# LED_Driver_-_2.net
KiCad netlist of a schematic drawn in Altium Designer
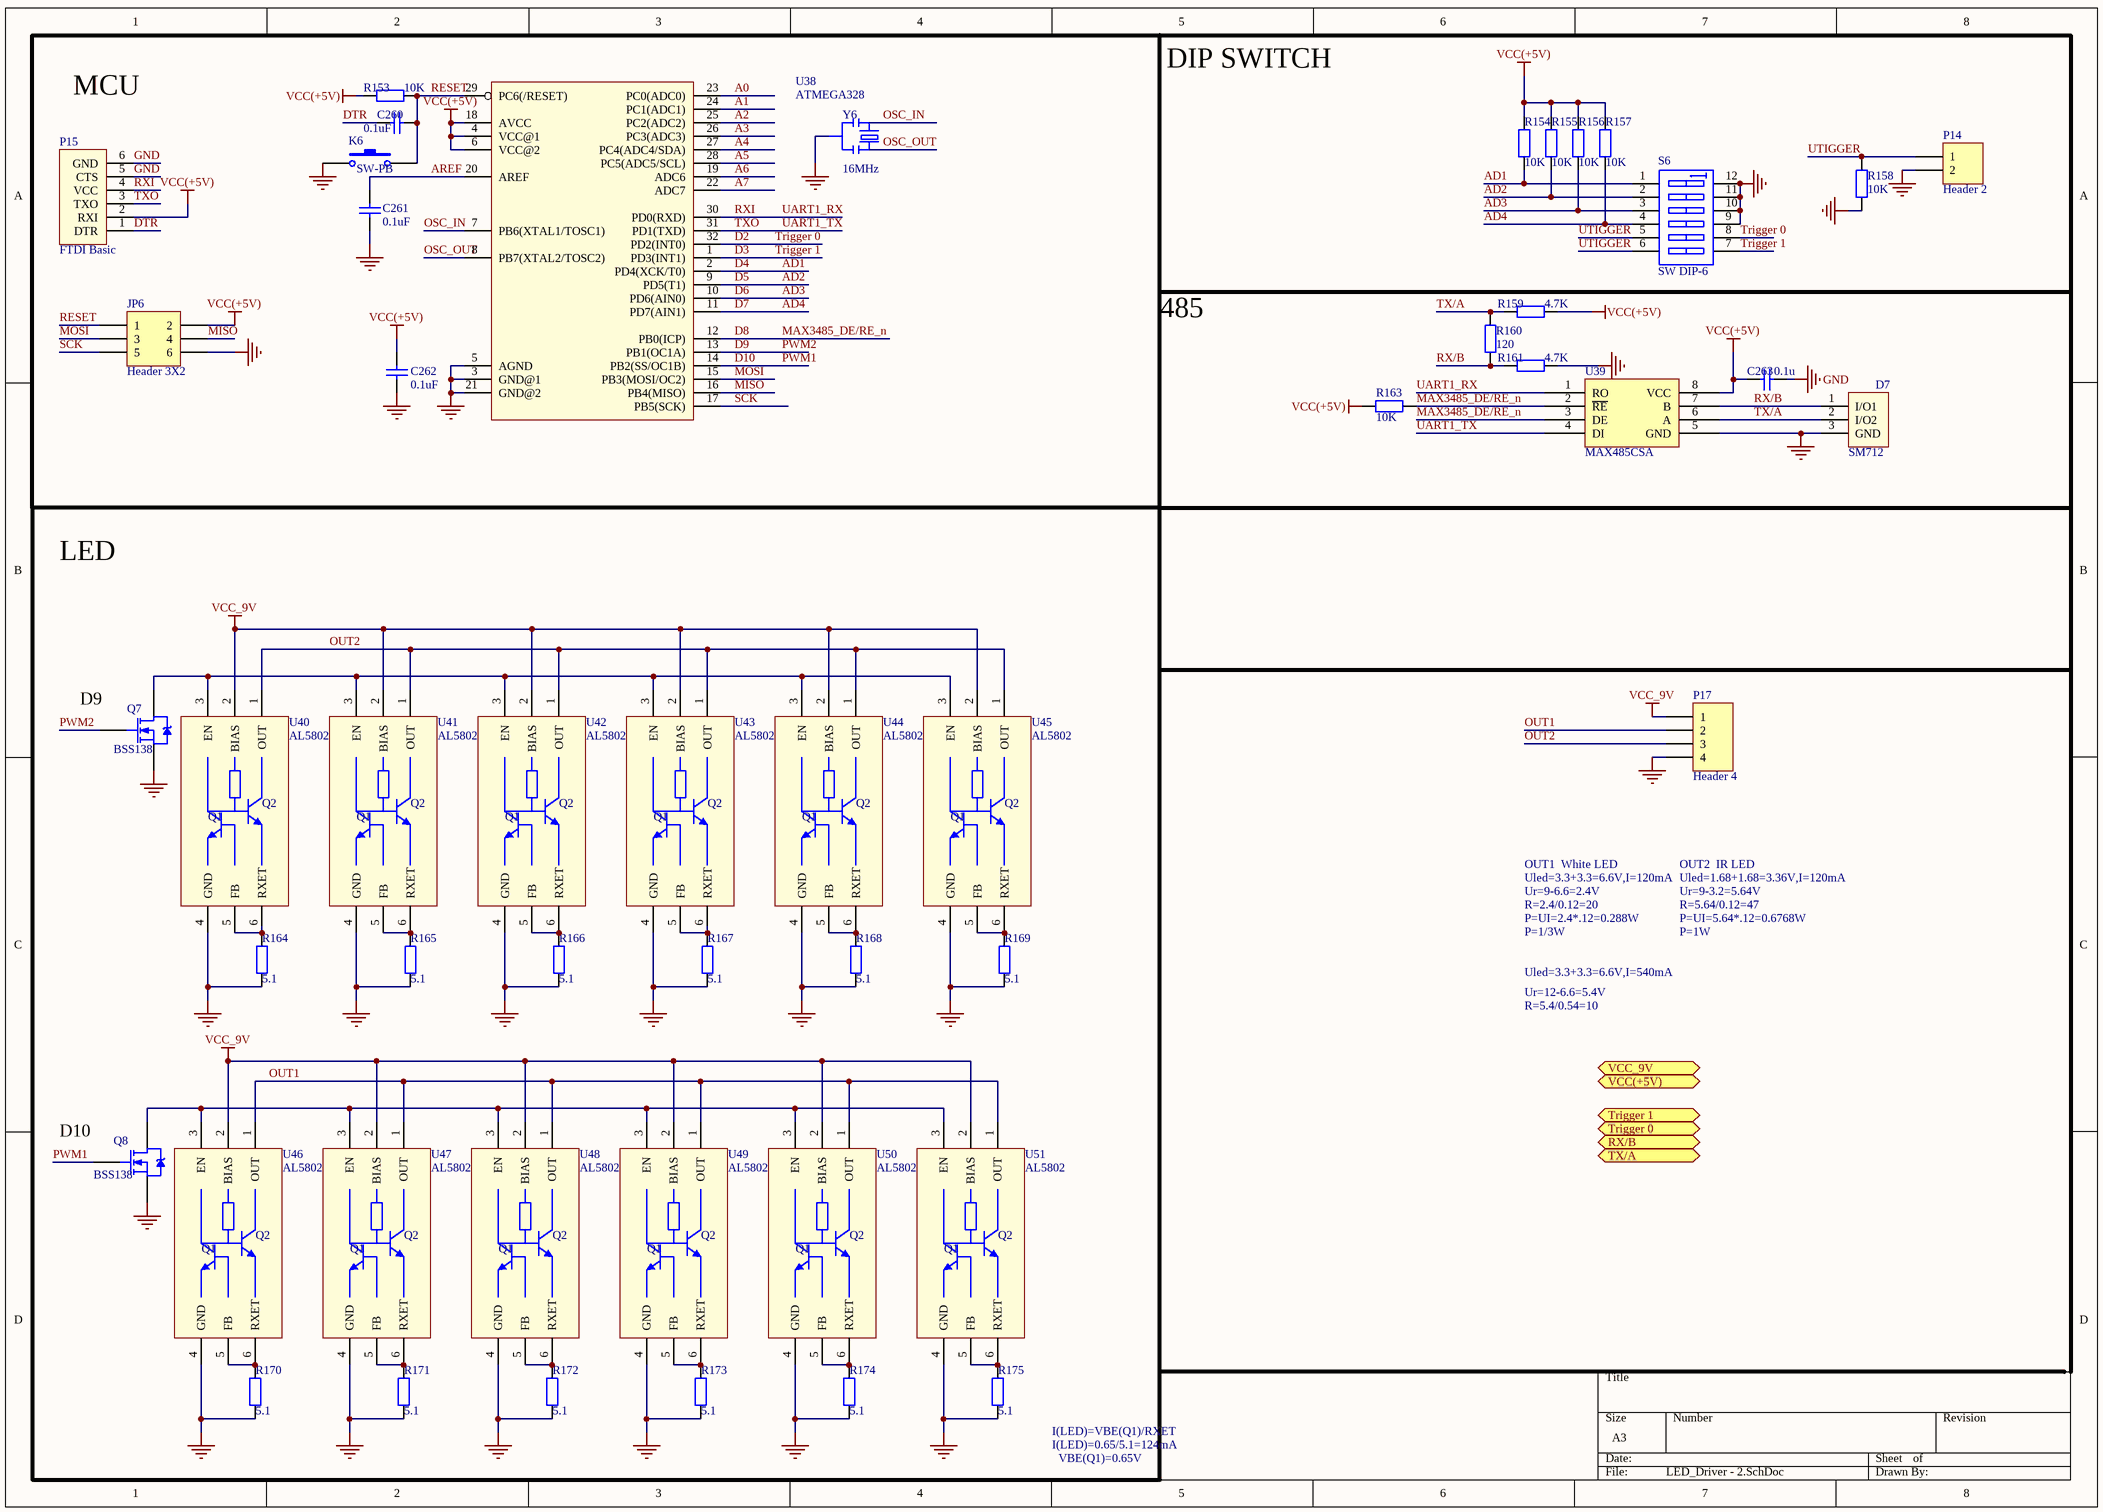
[diagram p0: LED_Driver - 2.SchDoc]

(export (version "E")
  (design (tool "Eeschema 10.0.6"))
  (components
    (comp (ref "C260")
      (value "0.1uF")
      (footprint "C0603")
      (description "Capacitor")
      (fields (field (name "IPARTNUMBER") "C100nF25V10%X7R") (field (name "VOLTAGE") "25V"))
      (libsource (lib "Schlib1") (part "CAP SMT C100nF25V10%X7R"))
    )
    (comp (ref "C261")
      (value "0.1uF")
      (footprint "C0603")
      (description "Capacitor")
      (fields (field (name "IPARTNUMBER") "C100nF25V10%X7R") (field (name "VOLTAGE") "25V"))
      (libsource (lib "Schlib1") (part "CAP SMT C100nF25V10%X7R"))
    )
    (comp (ref "C262")
      (value "0.1uF")
      (footprint "C0603")
      (description "Capacitor")
      (fields (field (name "IPARTNUMBER") "C100nF25V10%X7R") (field (name "VOLTAGE") "25V"))
      (libsource (lib "Schlib1") (part "CAP SMT C100nF25V10%X7R"))
    )
    (comp (ref "C263")
      (value "0.1u")
      (footprint "C0603")
      (description "Capacitor")
      (fields (field (name "PUBLISHER") "Altium Limited"))
      (libsource (lib "Miscellaneous Devices") (part "Cap"))
    )
    (comp (ref "D7")
      (value "SM712")
      (footprint "SOT23-3")
      (libsource (lib "STM32F4_CAM V2.0") (part "SM712"))
    )
    (comp (ref "JP6")
      (value "Header 3X2")
      (footprint "MHDR1X6")
      (description "Header, 3-Pin, Dual row")
      (fields (field (name "PUBLISHER") "Altium Limited"))
      (libsource (lib "Miscellaneous Connectors") (part "Header 3X2"))
    )
    (comp (ref "K6")
      (value "SW-PB")
      (footprint "157SW")
      (description "Switch")
      (fields (field (name "PUBLISHER") "Altium Limited"))
      (libsource (lib "Miscellaneous Devices") (part "SW-PB"))
    )
    (comp (ref "P14")
      (value "Header 2")
      (footprint "HDR1X2")
      (description "Header, 2-Pin")
      (fields (field (name "PUBLISHER") "Altium Limited"))
      (libsource (lib "Miscellaneous Connectors") (part "Header 2"))
    )
    (comp (ref "P15")
      (value "FTDI Basic")
      (footprint "MHDR1X6")
      (libsource (lib "PCB_Project1") (part "ARDUINO_SERIAL_PROGRAMPTH"))
    )
    (comp (ref "P17")
      (value "Header 4")
      (footprint "SMT_1.25MM*4")
      (description "Header, 4-Pin")
      (fields (field (name "PUBLISHER") "Altium Limited"))
      (libsource (lib "Miscellaneous Connectors") (part "Header 4"))
    )
    (comp (ref "Q7")
      (value "BSS138")
      (footprint "SOT-23 (Standard)")
      (fields
        (field (name "MANUFACTURER") "Fairchild Semiconductor")
        (field (name "MANUFACTURER PART NUMBER") "BSS123")
      )
      (libsource (lib "Miscellaneous_Devices") (part "NMOS"))
    )
    (comp (ref "Q8")
      (value "BSS138")
      (footprint "SOT-23 (Standard)")
      (fields
        (field (name "MANUFACTURER") "Fairchild Semiconductor")
        (field (name "MANUFACTURER PART NUMBER") "BSS123")
      )
      (libsource (lib "Miscellaneous_Devices") (part "NMOS"))
    )
    (comp (ref "R153")
      (value "10K")
      (footprint "R0603")
      (description "Resistor")
      (libsource (lib "") (part "Res2_2"))
    )
    (comp (ref "R154")
      (value "10K")
      (footprint "R0603")
      (description "Resistor")
      (libsource (lib "DM642") (part "Res2"))
    )
    (comp (ref "R155")
      (value "10K")
      (footprint "R0603")
      (description "Resistor")
      (libsource (lib "DM642") (part "Res2"))
    )
    (comp (ref "R156")
      (value "10K")
      (footprint "R0603")
      (description "Resistor")
      (libsource (lib "DM642") (part "Res2"))
    )
    (comp (ref "R157")
      (value "10K")
      (footprint "R0603")
      (description "Resistor")
      (libsource (lib "DM642") (part "Res2"))
    )
    (comp (ref "R158")
      (value "10K")
      (footprint "R0603")
      (description "Resistor")
      (fields (field (name "PUBLISHER") "Altium Limited"))
      (libsource (lib "Miscellaneous Devices") (part "Res2"))
    )
    (comp (ref "R159")
      (value "4.7K")
      (footprint "R0603")
      (description "Resistor")
      (libsource (lib "") (part "Res2_1"))
    )
    (comp (ref "R160")
      (value "120")
      (footprint "R0603")
      (description "Resistor")
      (libsource (lib "DM642") (part "Res2"))
    )
    (comp (ref "R161")
      (value "4.7K")
      (footprint "R0603")
      (description "Resistor")
      (libsource (lib "") (part "Res2_1"))
    )
    (comp (ref "R163")
      (value "10K")
      (footprint "R0603")
      (description "Resistor")
      (libsource (lib "") (part "Res2_1"))
    )
    (comp (ref "R164")
      (value "5.1")
      (footprint "R0603")
      (description "Resistor")
      (libsource (lib "DM642") (part "Res2"))
    )
    (comp (ref "R165")
      (value "5.1")
      (footprint "R0603")
      (description "Resistor")
      (libsource (lib "DM642") (part "Res2"))
    )
    (comp (ref "R166")
      (value "5.1")
      (footprint "R0603")
      (description "Resistor")
      (libsource (lib "DM642") (part "Res2"))
    )
    (comp (ref "R167")
      (value "5.1")
      (footprint "R0603")
      (description "Resistor")
      (libsource (lib "DM642") (part "Res2"))
    )
    (comp (ref "R168")
      (value "5.1")
      (footprint "R0603")
      (description "Resistor")
      (libsource (lib "DM642") (part "Res2"))
    )
    (comp (ref "R169")
      (value "5.1")
      (footprint "R0603")
      (description "Resistor")
      (libsource (lib "DM642") (part "Res2"))
    )
    (comp (ref "R170")
      (value "5.1")
      (footprint "R0603")
      (description "Resistor")
      (libsource (lib "DM642") (part "Res2"))
    )
    (comp (ref "R171")
      (value "5.1")
      (footprint "R0603")
      (description "Resistor")
      (libsource (lib "DM642") (part "Res2"))
    )
    (comp (ref "R172")
      (value "5.1")
      (footprint "R0603")
      (description "Resistor")
      (libsource (lib "DM642") (part "Res2"))
    )
    (comp (ref "R173")
      (value "5.1")
      (footprint "R0603")
      (description "Resistor")
      (libsource (lib "DM642") (part "Res2"))
    )
    (comp (ref "R174")
      (value "5.1")
      (footprint "R0603")
      (description "Resistor")
      (libsource (lib "DM642") (part "Res2"))
    )
    (comp (ref "R175")
      (value "5.1")
      (footprint "R0603")
      (description "Resistor")
      (libsource (lib "DM642") (part "Res2"))
    )
    (comp (ref "S6")
      (value "SW DIP-6")
      (footprint "DIP_SW_6WAY_SMD")
      (description "DIP Switch, 6 Position, SPST")
      (fields (field (name "PUBLISHER") "Altium Limited"))
      (libsource (lib "Miscellaneous Devices") (part "SW DIP-6"))
    )
    (comp (ref "U38")
      (value "ATMEGA328")
      (footprint "TQFP32-08")
      (libsource (lib "PCB_Project1") (part "ATMEGA168"))
    )
    (comp (ref "U39")
      (value "MAX485CSA")
      (footprint "SOIC-8")
      (libsource (lib "STM32F4_CAM V1.2") (part "MAX3485CSA"))
    )
    (comp (ref "U40") (value "AL5802") (footprint "SOT26") (libsource (lib "LED") (part "AL5802")))
    (comp (ref "U41") (value "AL5802") (footprint "SOT26") (libsource (lib "LED") (part "AL5802")))
    (comp (ref "U42") (value "AL5802") (footprint "SOT26") (libsource (lib "LED") (part "AL5802")))
    (comp (ref "U43") (value "AL5802") (footprint "SOT26") (libsource (lib "LED") (part "AL5802")))
    (comp (ref "U44") (value "AL5802") (footprint "SOT26") (libsource (lib "LED") (part "AL5802")))
    (comp (ref "U45") (value "AL5802") (footprint "SOT26") (libsource (lib "LED") (part "AL5802")))
    (comp (ref "U46") (value "AL5802") (footprint "SOT26") (libsource (lib "LED") (part "AL5802")))
    (comp (ref "U47") (value "AL5802") (footprint "SOT26") (libsource (lib "LED") (part "AL5802")))
    (comp (ref "U48") (value "AL5802") (footprint "SOT26") (libsource (lib "LED") (part "AL5802")))
    (comp (ref "U49") (value "AL5802") (footprint "SOT26") (libsource (lib "LED") (part "AL5802")))
    (comp (ref "U50") (value "AL5802") (footprint "SOT26") (libsource (lib "LED") (part "AL5802")))
    (comp (ref "U51") (value "AL5802") (footprint "SOT26") (libsource (lib "LED") (part "AL5802")))
    (comp (ref "Y6")
      (value "16MHz")
      (footprint "RESONATOR-SMD")
      (libsource (lib "SparkFun") (part "RESONATORSMD"))
    )
  )
  (nets
    (net (code "1") (name "/A0") (class "Default")
      (node (ref "U38") (pin "23") (pinfunction "PC0(ADC0)_23") (pintype "passive"))
    )
    (net (code "2") (name "/A1") (class "Default")
      (node (ref "U38") (pin "24") (pinfunction "PC1(ADC1)_24") (pintype "passive"))
    )
    (net (code "3") (name "/A2") (class "Default")
      (node (ref "U38") (pin "25") (pinfunction "PC2(ADC2)_25") (pintype "passive"))
    )
    (net (code "4") (name "/A3") (class "Default")
      (node (ref "U38") (pin "26") (pinfunction "PC3(ADC3)_26") (pintype "passive"))
    )
    (net (code "5") (name "/A4") (class "Default")
      (node (ref "U38") (pin "27") (pinfunction "PC4(ADC4/SDA)_27") (pintype "passive"))
    )
    (net (code "6") (name "/A5") (class "Default")
      (node (ref "U38") (pin "28") (pinfunction "PC5(ADC5/SCL)_28") (pintype "passive"))
    )
    (net (code "7") (name "/A6") (class "Default")
      (node (ref "U38") (pin "19") (pinfunction "ADC6_19") (pintype "passive"))
    )
    (net (code "8") (name "/A7") (class "Default")
      (node (ref "U38") (pin "22") (pinfunction "ADC7_22") (pintype "passive"))
    )
    (net (code "9") (name "/AD1") (class "Default")
      (node (ref "R154") (pin "2") (pinfunction "2_2") (pintype "passive"))
      (node (ref "S6") (pin "1") (pinfunction "A1_1") (pintype "passive"))
      (node (ref "U38") (pin "2") (pinfunction "PD4(XCK/T0)_2") (pintype "passive"))
    )
    (net (code "10") (name "/AD2") (class "Default")
      (node (ref "R155") (pin "2") (pinfunction "2_2") (pintype "passive"))
      (node (ref "S6") (pin "2") (pinfunction "A2_2") (pintype "passive"))
      (node (ref "U38") (pin "9") (pinfunction "PD5(T1)_9") (pintype "passive"))
    )
    (net (code "11") (name "/AD3") (class "Default")
      (node (ref "R156") (pin "2") (pinfunction "2_2") (pintype "passive"))
      (node (ref "S6") (pin "3") (pinfunction "A3_3") (pintype "passive"))
      (node (ref "U38") (pin "10") (pinfunction "PD6(AIN0)_10") (pintype "passive"))
    )
    (net (code "12") (name "/AD4") (class "Default")
      (node (ref "R157") (pin "2") (pinfunction "2_2") (pintype "passive"))
      (node (ref "S6") (pin "4") (pinfunction "A4_4") (pintype "passive"))
      (node (ref "U38") (pin "11") (pinfunction "PD7(AIN1)_11") (pintype "passive"))
    )
    (net (code "13") (name "/AREF") (class "Default")
      (node (ref "C261") (pin "2") (pinfunction "2_2") (pintype "passive"))
      (node (ref "U38") (pin "20") (pinfunction "AREF_20") (pintype "passive"))
    )
    (net (code "14") (name "/D2") (class "Default")
      (node (ref "S6") (pin "8") (pinfunction "B5_8") (pintype "passive"))
      (node (ref "U38") (pin "32") (pinfunction "PD2(INT0)_32") (pintype "passive"))
    )
    (net (code "15") (name "/D3") (class "Default")
      (node (ref "S6") (pin "7") (pinfunction "B6_7") (pintype "passive"))
      (node (ref "U38") (pin "1") (pinfunction "PD3(INT1)_1") (pintype "passive"))
    )
    (net (code "16") (name "/D8") (class "Default")
      (node (ref "R163") (pin "1") (pinfunction "1_1") (pintype "passive"))
      (node (ref "U38") (pin "12") (pinfunction "PB0(ICP)_12") (pintype "passive"))
      (node (ref "U39") (pin "2") (pinfunction "~{RE}_2") (pintype "passive"))
      (node (ref "U39") (pin "3") (pinfunction "DE_3") (pintype "passive"))
    )
    (net (code "17") (name "/D9") (class "Default")
      (node (ref "Q7") (pin "G") (pinfunction "G_G") (pintype "passive"))
      (node (ref "U38") (pin "13") (pinfunction "PB1(OC1A)_13") (pintype "passive"))
    )
    (net (code "18") (name "/D10") (class "Default")
      (node (ref "Q8") (pin "G") (pinfunction "G_G") (pintype "passive"))
      (node (ref "U38") (pin "14") (pinfunction "PB2(SS/OC1B)_14") (pintype "passive"))
    )
    (net (code "19") (name "/DTR") (class "Default")
      (node (ref "C260") (pin "1") (pinfunction "1_1") (pintype "passive"))
      (node (ref "P15") (pin "1") (pinfunction "DTR_1") (pintype "passive"))
    )
    (net (code "20") (name "/MISO") (class "Default")
      (node (ref "JP6") (pin "4") (pinfunction "4_4") (pintype "passive"))
      (node (ref "U38") (pin "16") (pinfunction "PB4(MISO)_16") (pintype "passive"))
    )
    (net (code "21") (name "/MOSI") (class "Default")
      (node (ref "JP6") (pin "3") (pinfunction "3_3") (pintype "passive"))
      (node (ref "U38") (pin "15") (pinfunction "PB3(MOSI/OC2)_15") (pintype "passive"))
    )
    (net (code "22") (name "/OSC_IN") (class "Default")
      (node (ref "U38") (pin "7") (pinfunction "PB6(XTAL1/TOSC1)_7") (pintype "passive"))
      (node (ref "Y6") (pin "3") (pinfunction "3_3") (pintype "passive"))
    )
    (net (code "23") (name "/OSC_OUT") (class "Default")
      (node (ref "U38") (pin "8") (pinfunction "PB7(XTAL2/TOSC2)_8") (pintype "passive"))
      (node (ref "Y6") (pin "1") (pinfunction "1_1") (pintype "passive"))
    )
    (net (code "24") (name "/OUT1") (class "Default")
      (node (ref "P17") (pin "2") (pinfunction "2_2") (pintype "passive"))
      (node (ref "U46") (pin "1") (pinfunction "OUT_1") (pintype "passive"))
      (node (ref "U47") (pin "1") (pinfunction "OUT_1") (pintype "passive"))
      (node (ref "U48") (pin "1") (pinfunction "OUT_1") (pintype "passive"))
      (node (ref "U49") (pin "1") (pinfunction "OUT_1") (pintype "passive"))
      (node (ref "U50") (pin "1") (pinfunction "OUT_1") (pintype "passive"))
      (node (ref "U51") (pin "1") (pinfunction "OUT_1") (pintype "passive"))
    )
    (net (code "25") (name "/OUT2") (class "Default")
      (node (ref "P17") (pin "3") (pinfunction "3_3") (pintype "passive"))
      (node (ref "U40") (pin "1") (pinfunction "OUT_1") (pintype "passive"))
      (node (ref "U41") (pin "1") (pinfunction "OUT_1") (pintype "passive"))
      (node (ref "U42") (pin "1") (pinfunction "OUT_1") (pintype "passive"))
      (node (ref "U43") (pin "1") (pinfunction "OUT_1") (pintype "passive"))
      (node (ref "U44") (pin "1") (pinfunction "OUT_1") (pintype "passive"))
      (node (ref "U45") (pin "1") (pinfunction "OUT_1") (pintype "passive"))
    )
    (net (code "26") (name "/RESET") (class "Default")
      (node (ref "C260") (pin "2") (pinfunction "2_2") (pintype "passive"))
      (node (ref "JP6") (pin "1") (pinfunction "1_1") (pintype "passive"))
      (node (ref "K6") (pin "2") (pinfunction "2_2") (pintype "passive"))
      (node (ref "R153") (pin "2") (pinfunction "2_2") (pintype "passive"))
      (node (ref "U38") (pin "29") (pinfunction "PC6(/RESET)_29") (pintype "passive"))
    )
    (net (code "27") (name "/RXI") (class "Default")
      (node (ref "P15") (pin "4") (pinfunction "VCC_4") (pintype "passive"))
      (node (ref "U38") (pin "30") (pinfunction "PD0(RXD)_30") (pintype "passive"))
      (node (ref "U39") (pin "1") (pinfunction "RO_1") (pintype "passive"))
    )
    (net (code "28") (name "/RX{slash}B") (class "Default")
      (node (ref "D7") (pin "1") (pinfunction "I/O1_1") (pintype "passive"))
      (node (ref "R160") (pin "2") (pinfunction "2_2") (pintype "passive"))
      (node (ref "R161") (pin "2") (pinfunction "2_2") (pintype "passive"))
      (node (ref "U39") (pin "7") (pinfunction "B_7") (pintype "passive"))
    )
    (net (code "29") (name "/SCK") (class "Default")
      (node (ref "JP6") (pin "5") (pinfunction "5_5") (pintype "passive"))
      (node (ref "U38") (pin "17") (pinfunction "PB5(SCK)_17") (pintype "passive"))
    )
    (net (code "30") (name "/TXO") (class "Default")
      (node (ref "P15") (pin "3") (pinfunction "TXO_3") (pintype "passive"))
      (node (ref "U38") (pin "31") (pinfunction "PD1(TXD)_31") (pintype "passive"))
      (node (ref "U39") (pin "4") (pinfunction "DI_4") (pintype "passive"))
    )
    (net (code "31") (name "/TX{slash}A") (class "Default")
      (node (ref "D7") (pin "2") (pinfunction "I/O2_2") (pintype "passive"))
      (node (ref "R159") (pin "2") (pinfunction "2_2") (pintype "passive"))
      (node (ref "R160") (pin "1") (pinfunction "1_1") (pintype "passive"))
      (node (ref "U39") (pin "6") (pinfunction "A_6") (pintype "passive"))
    )
    (net (code "32") (name "/UTIGGER") (class "Default")
      (node (ref "P14") (pin "1") (pinfunction "1_1") (pintype "passive"))
      (node (ref "R158") (pin "2") (pinfunction "2_2") (pintype "passive"))
      (node (ref "S6") (pin "5") (pinfunction "A5_5") (pintype "passive"))
      (node (ref "S6") (pin "6") (pinfunction "A6_6") (pintype "passive"))
    )
    (net (code "33") (name "GND") (class "Default")
      (node (ref "C261") (pin "1") (pinfunction "1_1") (pintype "passive"))
      (node (ref "C262") (pin "2") (pinfunction "2_2") (pintype "passive"))
      (node (ref "C263") (pin "1") (pinfunction "1_1") (pintype "passive"))
      (node (ref "D7") (pin "3") (pinfunction "GND_3") (pintype "passive"))
      (node (ref "JP6") (pin "6") (pinfunction "6_6") (pintype "passive"))
      (node (ref "K6") (pin "1") (pinfunction "1_1") (pintype "passive"))
      (node (ref "P14") (pin "2") (pinfunction "2_2") (pintype "passive"))
      (node (ref "P15") (pin "5") (pinfunction "CTS_5") (pintype "passive"))
      (node (ref "P15") (pin "6") (pinfunction "GND_6") (pintype "passive"))
      (node (ref "P17") (pin "4") (pinfunction "4_4") (pintype "passive"))
      (node (ref "Q7") (pin "S") (pinfunction "S_S") (pintype "passive"))
      (node (ref "Q8") (pin "S") (pinfunction "S_S") (pintype "passive"))
      (node (ref "R158") (pin "1") (pinfunction "1_1") (pintype "passive"))
      (node (ref "R161") (pin "1") (pinfunction "1_1") (pintype "passive"))
      (node (ref "R164") (pin "2") (pinfunction "2_2") (pintype "passive"))
      (node (ref "R165") (pin "2") (pinfunction "2_2") (pintype "passive"))
      (node (ref "R166") (pin "2") (pinfunction "2_2") (pintype "passive"))
      (node (ref "R167") (pin "2") (pinfunction "2_2") (pintype "passive"))
      (node (ref "R168") (pin "2") (pinfunction "2_2") (pintype "passive"))
      (node (ref "R169") (pin "2") (pinfunction "2_2") (pintype "passive"))
      (node (ref "R170") (pin "2") (pinfunction "2_2") (pintype "passive"))
      (node (ref "R171") (pin "2") (pinfunction "2_2") (pintype "passive"))
      (node (ref "R172") (pin "2") (pinfunction "2_2") (pintype "passive"))
      (node (ref "R173") (pin "2") (pinfunction "2_2") (pintype "passive"))
      (node (ref "R174") (pin "2") (pinfunction "2_2") (pintype "passive"))
      (node (ref "R175") (pin "2") (pinfunction "2_2") (pintype "passive"))
      (node (ref "S6") (pin "10") (pinfunction "B3_10") (pintype "passive"))
      (node (ref "S6") (pin "11") (pinfunction "B2_11") (pintype "passive"))
      (node (ref "S6") (pin "12") (pinfunction "B1_12") (pintype "passive"))
      (node (ref "S6") (pin "9") (pinfunction "B4_9") (pintype "passive"))
      (node (ref "U38") (pin "21") (pinfunction "GND@2_21") (pintype "passive"))
      (node (ref "U38") (pin "3") (pinfunction "GND@1_3") (pintype "passive"))
      (node (ref "U38") (pin "5") (pinfunction "AGND_5") (pintype "passive"))
      (node (ref "U39") (pin "5") (pinfunction "GND_5") (pintype "passive"))
      (node (ref "U40") (pin "4") (pinfunction "GND_4") (pintype "passive"))
      (node (ref "U41") (pin "4") (pinfunction "GND_4") (pintype "passive"))
      (node (ref "U42") (pin "4") (pinfunction "GND_4") (pintype "passive"))
      (node (ref "U43") (pin "4") (pinfunction "GND_4") (pintype "passive"))
      (node (ref "U44") (pin "4") (pinfunction "GND_4") (pintype "passive"))
      (node (ref "U45") (pin "4") (pinfunction "GND_4") (pintype "passive"))
      (node (ref "U46") (pin "4") (pinfunction "GND_4") (pintype "passive"))
      (node (ref "U47") (pin "4") (pinfunction "GND_4") (pintype "passive"))
      (node (ref "U48") (pin "4") (pinfunction "GND_4") (pintype "passive"))
      (node (ref "U49") (pin "4") (pinfunction "GND_4") (pintype "passive"))
      (node (ref "U50") (pin "4") (pinfunction "GND_4") (pintype "passive"))
      (node (ref "U51") (pin "4") (pinfunction "GND_4") (pintype "passive"))
      (node (ref "Y6") (pin "2") (pinfunction "2_2") (pintype "passive"))
    )
    (net (code "34") (name "Net-(U40-EN)") (class "Default")
      (node (ref "Q7") (pin "D") (pinfunction "D_D") (pintype "passive"))
      (node (ref "U40") (pin "3") (pinfunction "EN_3") (pintype "passive"))
      (node (ref "U41") (pin "3") (pinfunction "EN_3") (pintype "passive"))
      (node (ref "U42") (pin "3") (pinfunction "EN_3") (pintype "passive"))
      (node (ref "U43") (pin "3") (pinfunction "EN_3") (pintype "passive"))
      (node (ref "U44") (pin "3") (pinfunction "EN_3") (pintype "passive"))
      (node (ref "U45") (pin "3") (pinfunction "EN_3") (pintype "passive"))
    )
    (net (code "35") (name "Net-(U40-FB)") (class "Default")
      (node (ref "R164") (pin "1") (pinfunction "1_1") (pintype "passive"))
      (node (ref "U40") (pin "5") (pinfunction "FB_5") (pintype "passive"))
      (node (ref "U40") (pin "6") (pinfunction "RXET_6") (pintype "passive"))
    )
    (net (code "36") (name "Net-(U41-FB)") (class "Default")
      (node (ref "R165") (pin "1") (pinfunction "1_1") (pintype "passive"))
      (node (ref "U41") (pin "5") (pinfunction "FB_5") (pintype "passive"))
      (node (ref "U41") (pin "6") (pinfunction "RXET_6") (pintype "passive"))
    )
    (net (code "37") (name "Net-(U42-FB)") (class "Default")
      (node (ref "R166") (pin "1") (pinfunction "1_1") (pintype "passive"))
      (node (ref "U42") (pin "5") (pinfunction "FB_5") (pintype "passive"))
      (node (ref "U42") (pin "6") (pinfunction "RXET_6") (pintype "passive"))
    )
    (net (code "38") (name "Net-(U43-FB)") (class "Default")
      (node (ref "R167") (pin "1") (pinfunction "1_1") (pintype "passive"))
      (node (ref "U43") (pin "5") (pinfunction "FB_5") (pintype "passive"))
      (node (ref "U43") (pin "6") (pinfunction "RXET_6") (pintype "passive"))
    )
    (net (code "39") (name "Net-(U44-FB)") (class "Default")
      (node (ref "R168") (pin "1") (pinfunction "1_1") (pintype "passive"))
      (node (ref "U44") (pin "5") (pinfunction "FB_5") (pintype "passive"))
      (node (ref "U44") (pin "6") (pinfunction "RXET_6") (pintype "passive"))
    )
    (net (code "40") (name "Net-(U45-FB)") (class "Default")
      (node (ref "R169") (pin "1") (pinfunction "1_1") (pintype "passive"))
      (node (ref "U45") (pin "5") (pinfunction "FB_5") (pintype "passive"))
      (node (ref "U45") (pin "6") (pinfunction "RXET_6") (pintype "passive"))
    )
    (net (code "41") (name "Net-(U46-EN)") (class "Default")
      (node (ref "Q8") (pin "D") (pinfunction "D_D") (pintype "passive"))
      (node (ref "U46") (pin "3") (pinfunction "EN_3") (pintype "passive"))
      (node (ref "U47") (pin "3") (pinfunction "EN_3") (pintype "passive"))
      (node (ref "U48") (pin "3") (pinfunction "EN_3") (pintype "passive"))
      (node (ref "U49") (pin "3") (pinfunction "EN_3") (pintype "passive"))
      (node (ref "U50") (pin "3") (pinfunction "EN_3") (pintype "passive"))
      (node (ref "U51") (pin "3") (pinfunction "EN_3") (pintype "passive"))
    )
    (net (code "42") (name "Net-(U46-FB)") (class "Default")
      (node (ref "R170") (pin "1") (pinfunction "1_1") (pintype "passive"))
      (node (ref "U46") (pin "5") (pinfunction "FB_5") (pintype "passive"))
      (node (ref "U46") (pin "6") (pinfunction "RXET_6") (pintype "passive"))
    )
    (net (code "43") (name "Net-(U47-FB)") (class "Default")
      (node (ref "R171") (pin "1") (pinfunction "1_1") (pintype "passive"))
      (node (ref "U47") (pin "5") (pinfunction "FB_5") (pintype "passive"))
      (node (ref "U47") (pin "6") (pinfunction "RXET_6") (pintype "passive"))
    )
    (net (code "44") (name "Net-(U48-FB)") (class "Default")
      (node (ref "R172") (pin "1") (pinfunction "1_1") (pintype "passive"))
      (node (ref "U48") (pin "5") (pinfunction "FB_5") (pintype "passive"))
      (node (ref "U48") (pin "6") (pinfunction "RXET_6") (pintype "passive"))
    )
    (net (code "45") (name "Net-(U49-FB)") (class "Default")
      (node (ref "R173") (pin "1") (pinfunction "1_1") (pintype "passive"))
      (node (ref "U49") (pin "5") (pinfunction "FB_5") (pintype "passive"))
      (node (ref "U49") (pin "6") (pinfunction "RXET_6") (pintype "passive"))
    )
    (net (code "46") (name "Net-(U50-FB)") (class "Default")
      (node (ref "R174") (pin "1") (pinfunction "1_1") (pintype "passive"))
      (node (ref "U50") (pin "5") (pinfunction "FB_5") (pintype "passive"))
      (node (ref "U50") (pin "6") (pinfunction "RXET_6") (pintype "passive"))
    )
    (net (code "47") (name "Net-(U51-FB)") (class "Default")
      (node (ref "R175") (pin "1") (pinfunction "1_1") (pintype "passive"))
      (node (ref "U51") (pin "5") (pinfunction "FB_5") (pintype "passive"))
      (node (ref "U51") (pin "6") (pinfunction "RXET_6") (pintype "passive"))
    )
    (net (code "48") (name "VCC(+5V)") (class "Default")
      (node (ref "C262") (pin "1") (pinfunction "1_1") (pintype "passive"))
      (node (ref "C263") (pin "2") (pinfunction "2_2") (pintype "passive"))
      (node (ref "JP6") (pin "2") (pinfunction "2_2") (pintype "passive"))
      (node (ref "P15") (pin "2") (pinfunction "RXI_2") (pintype "passive"))
      (node (ref "R153") (pin "1") (pinfunction "1_1") (pintype "passive"))
      (node (ref "R154") (pin "1") (pinfunction "1_1") (pintype "passive"))
      (node (ref "R155") (pin "1") (pinfunction "1_1") (pintype "passive"))
      (node (ref "R156") (pin "1") (pinfunction "1_1") (pintype "passive"))
      (node (ref "R157") (pin "1") (pinfunction "1_1") (pintype "passive"))
      (node (ref "R159") (pin "1") (pinfunction "1_1") (pintype "passive"))
      (node (ref "R163") (pin "2") (pinfunction "2_2") (pintype "passive"))
      (node (ref "U38") (pin "18") (pinfunction "AVCC_18") (pintype "passive"))
      (node (ref "U38") (pin "4") (pinfunction "VCC@1_4") (pintype "passive"))
      (node (ref "U38") (pin "6") (pinfunction "VCC@2_6") (pintype "passive"))
      (node (ref "U39") (pin "8") (pinfunction "VCC_8") (pintype "passive"))
    )
    (net (code "49") (name "VCC_9V") (class "Default")
      (node (ref "P17") (pin "1") (pinfunction "1_1") (pintype "passive"))
      (node (ref "U40") (pin "2") (pinfunction "BIAS_2") (pintype "passive"))
      (node (ref "U41") (pin "2") (pinfunction "BIAS_2") (pintype "passive"))
      (node (ref "U42") (pin "2") (pinfunction "BIAS_2") (pintype "passive"))
      (node (ref "U43") (pin "2") (pinfunction "BIAS_2") (pintype "passive"))
      (node (ref "U44") (pin "2") (pinfunction "BIAS_2") (pintype "passive"))
      (node (ref "U45") (pin "2") (pinfunction "BIAS_2") (pintype "passive"))
      (node (ref "U46") (pin "2") (pinfunction "BIAS_2") (pintype "passive"))
      (node (ref "U47") (pin "2") (pinfunction "BIAS_2") (pintype "passive"))
      (node (ref "U48") (pin "2") (pinfunction "BIAS_2") (pintype "passive"))
      (node (ref "U49") (pin "2") (pinfunction "BIAS_2") (pintype "passive"))
      (node (ref "U50") (pin "2") (pinfunction "BIAS_2") (pintype "passive"))
      (node (ref "U51") (pin "2") (pinfunction "BIAS_2") (pintype "passive"))
    )
  )
)
